# js220_fp_binding_posts.net
KiCad netlist of a schematic drawn in EAGLE
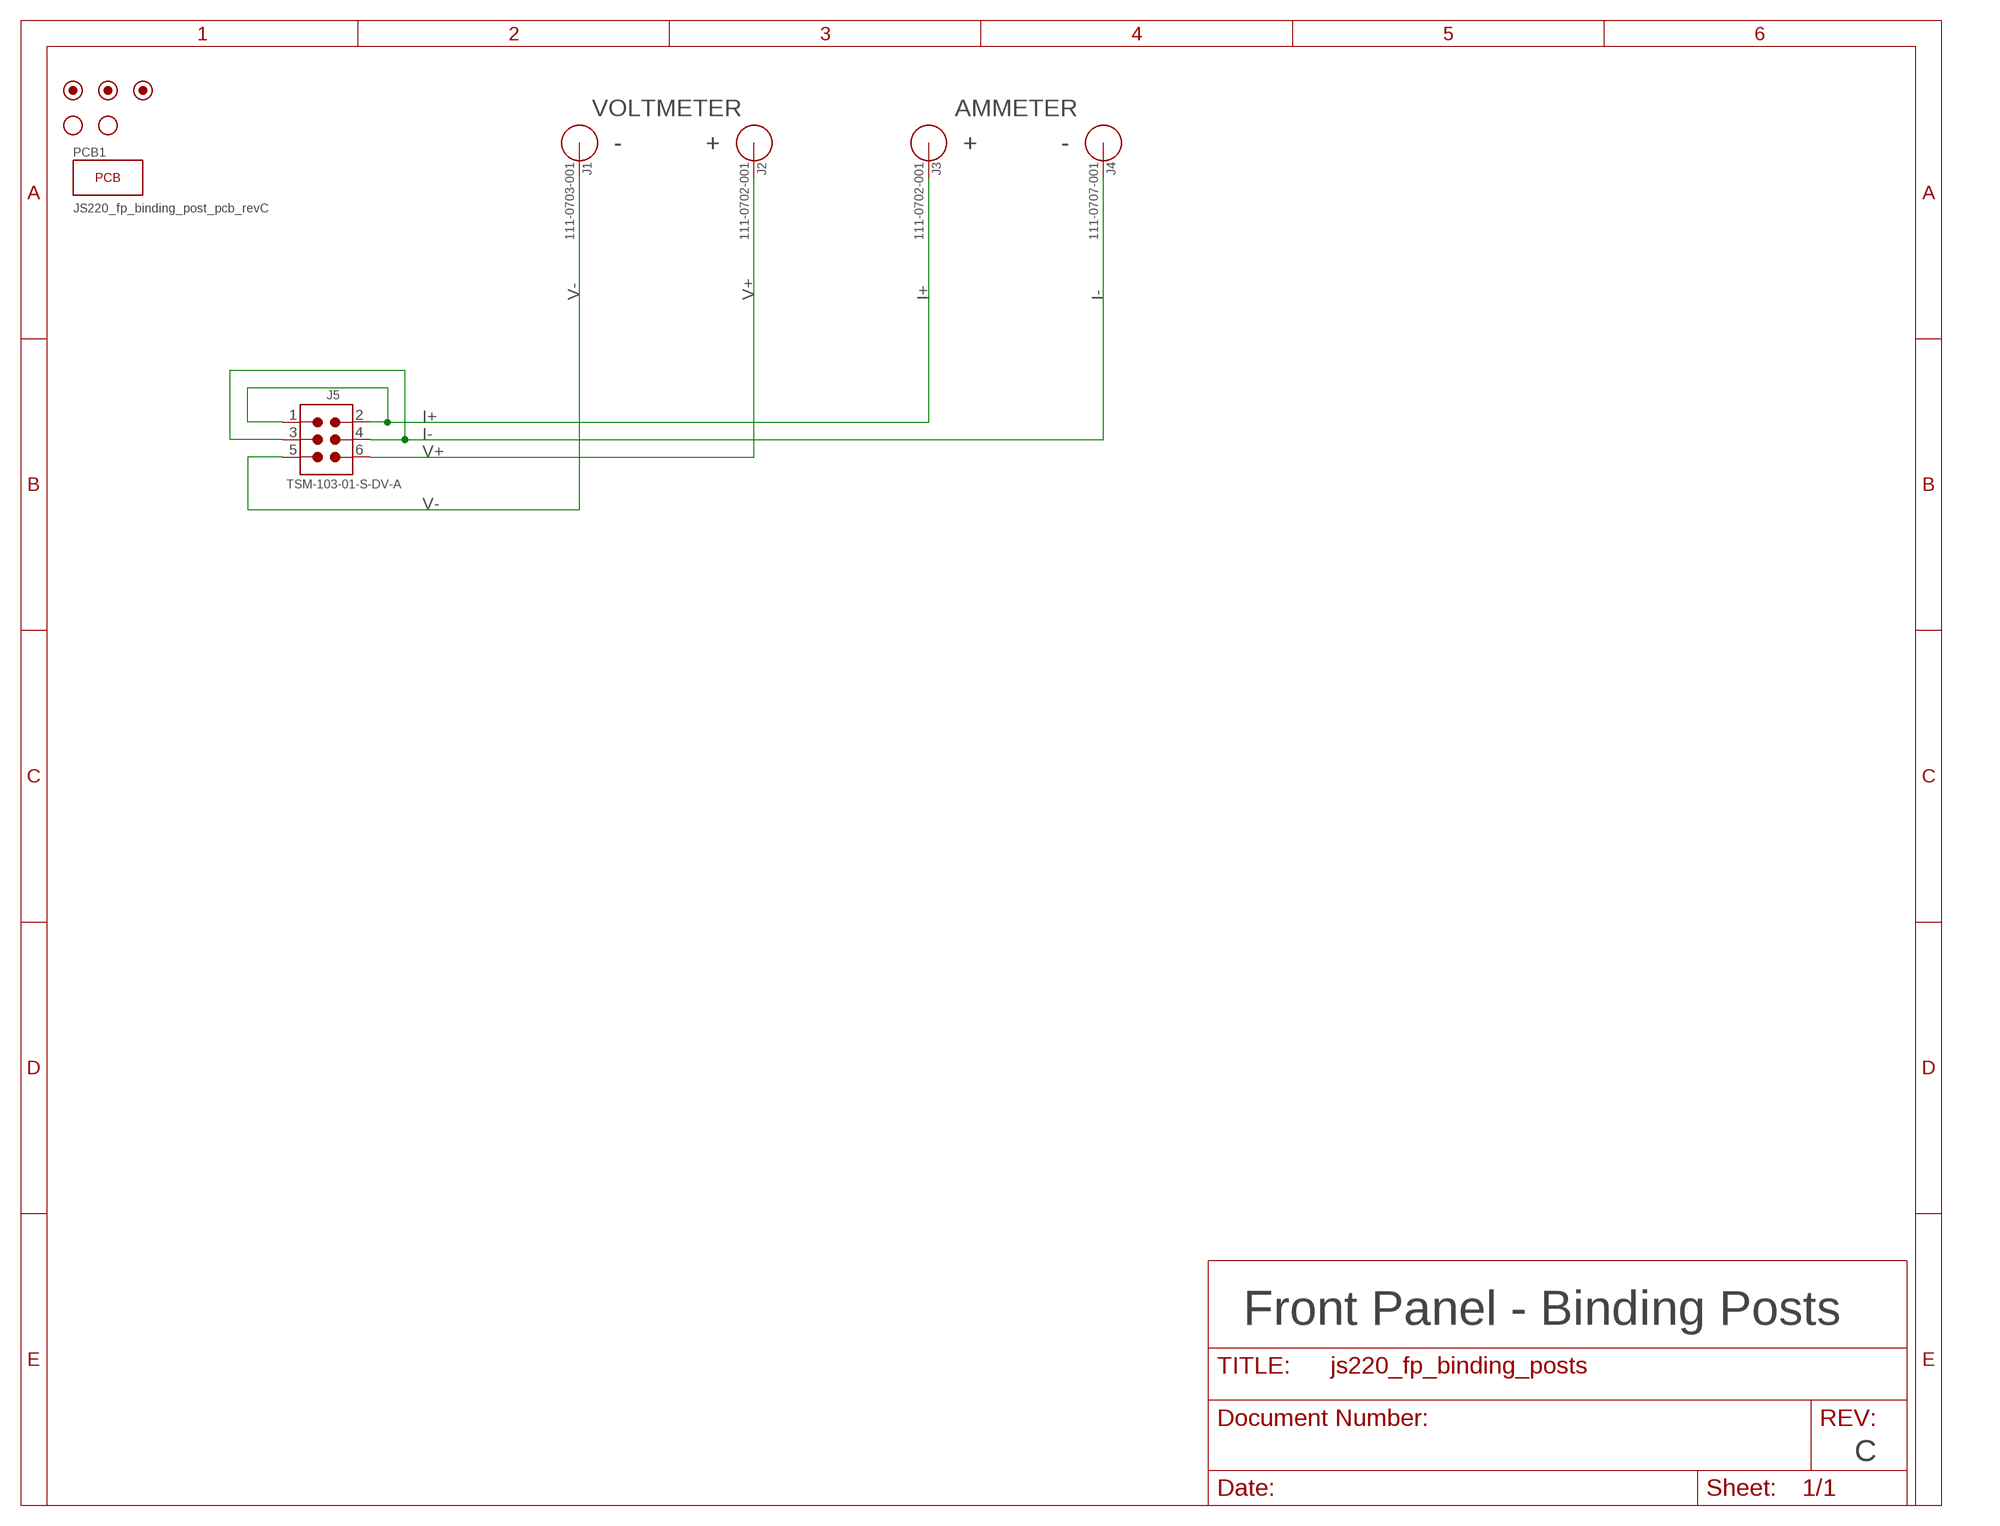
[diagram p0: schematic, sheet 1]

(export (version "E")
  (design (tool "Eeschema 10.0.6"))
  (components
    (comp (ref "FUD1")
      (value "FIDUCIAL_1MM")
      (footprint "eagle-import:FIDUCIAL_1MM_2MM")
      (libsource (lib "eagle-import") (part "FIDUCIAL_1MM"))
    )
    (comp (ref "FUD2")
      (value "FIDUCIAL_1MM")
      (footprint "eagle-import:FIDUCIAL_1MM_2MM")
      (libsource (lib "eagle-import") (part "FIDUCIAL_1MM"))
    )
    (comp (ref "FUD3")
      (value "FIDUCIAL_1MM")
      (footprint "eagle-import:FIDUCIAL_1MM_2MM")
      (libsource (lib "eagle-import") (part "FIDUCIAL_1MM"))
    )
    (comp (ref "H1")
      (value "HOLE_#6_NORESTRICT")
      (footprint "eagle-import:HOLE_3.5MM_NORESTRICT")
      (libsource (lib "eagle-import") (part "HOLE_#6_NORESTRICT"))
    )
    (comp (ref "H2")
      (value "HOLE_#6_NORESTRICT")
      (footprint "eagle-import:HOLE_3.5MM_NORESTRICT")
      (libsource (lib "eagle-import") (part "HOLE_#6_NORESTRICT"))
    )
    (comp (ref "J1")
      (value "111-0703-001")
      (footprint "eagle-import:BINDING_POST_6")
      (libsource (lib "eagle-import") (part "BINDING_POST_6"))
    )
    (comp (ref "J2")
      (value "111-0702-001")
      (footprint "eagle-import:BINDING_POST_6")
      (libsource (lib "eagle-import") (part "BINDING_POST_6"))
    )
    (comp (ref "J3")
      (value "111-0702-001")
      (footprint "eagle-import:BINDING_POST_6")
      (libsource (lib "eagle-import") (part "BINDING_POST_6"))
    )
    (comp (ref "J4")
      (value "111-0707-001")
      (footprint "eagle-import:BINDING_POST_6")
      (libsource (lib "eagle-import") (part "BINDING_POST_6"))
    )
    (comp (ref "J5")
      (value "TSM-103-01-S-DV-A")
      (footprint "eagle-import:CONN_0.1_3X2_MSA")
      (libsource (lib "eagle-import") (part "CONN_0.1_3X2_MSA"))
    )
  )
  (nets
    (net (code "1") (name "/I+") (class "Default")
      (node (ref "J3") (pin "1") (pinfunction "1_1") (pintype "bidirectional"))
      (node (ref "J5") (pin "1") (pinfunction "1_1") (pintype "bidirectional"))
      (node (ref "J5") (pin "2") (pinfunction "2_2") (pintype "bidirectional"))
    )
    (net (code "2") (name "/I-") (class "Default")
      (node (ref "J4") (pin "1") (pinfunction "1_1") (pintype "bidirectional"))
      (node (ref "J5") (pin "3") (pinfunction "3_3") (pintype "bidirectional"))
      (node (ref "J5") (pin "4") (pinfunction "4_4") (pintype "bidirectional"))
    )
    (net (code "3") (name "/V+") (class "Default")
      (node (ref "J2") (pin "1") (pinfunction "1_1") (pintype "bidirectional"))
      (node (ref "J5") (pin "6") (pinfunction "6_6") (pintype "bidirectional"))
    )
    (net (code "4") (name "/V-") (class "Default")
      (node (ref "J1") (pin "1") (pinfunction "1_1") (pintype "bidirectional"))
      (node (ref "J5") (pin "5") (pinfunction "5_5") (pintype "bidirectional"))
    )
  )
)
